# connectors.net
KiCad netlist of a schematic drawn in Altium Designer
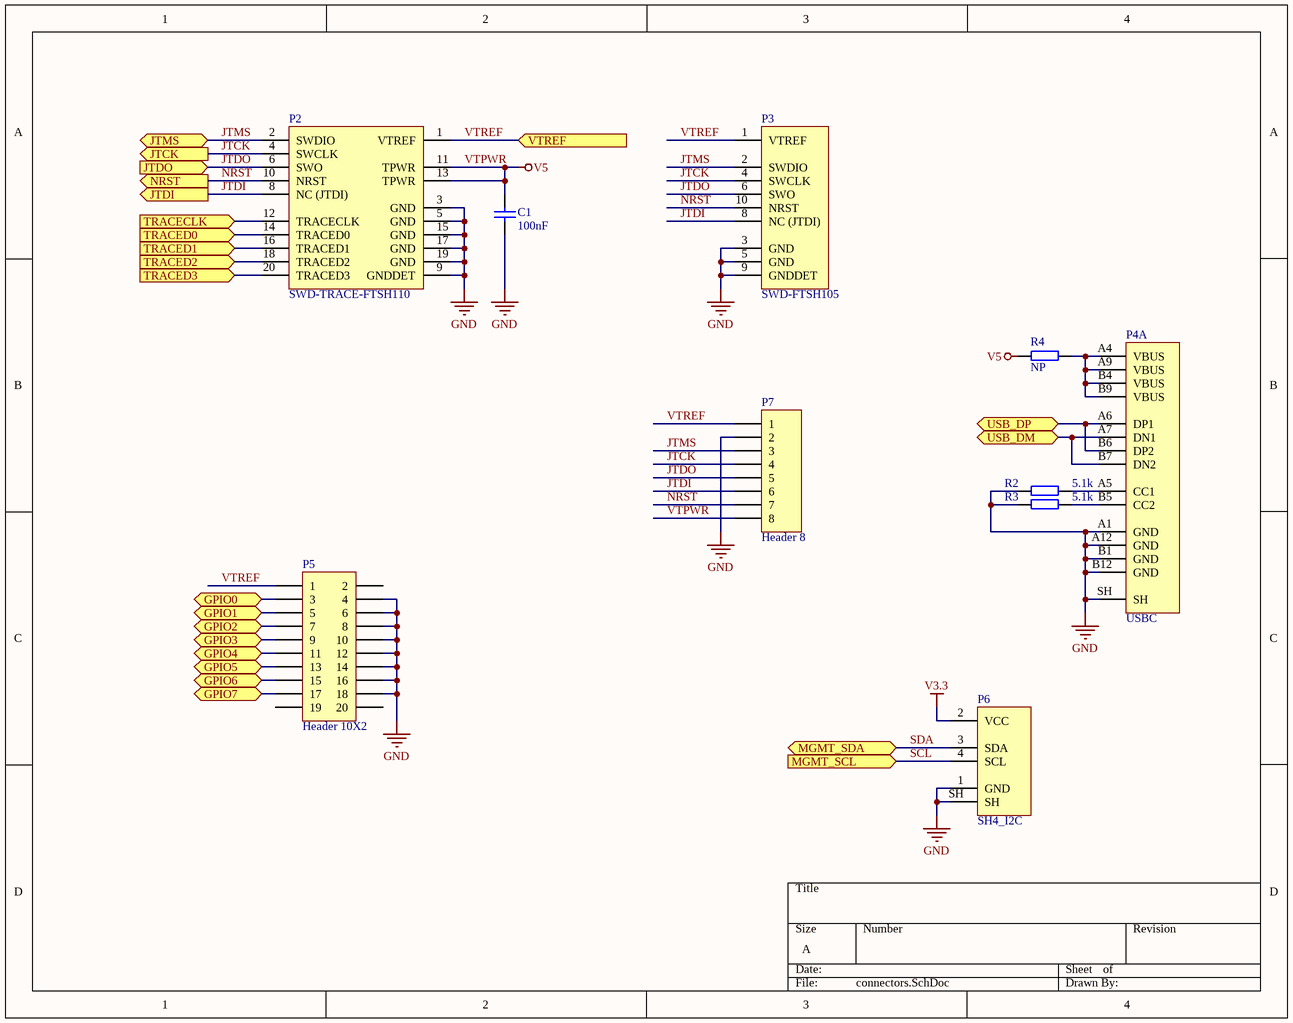
[diagram p0: connectors.SchDoc]

(export (version "E")
  (design (tool "Eeschema 10.0.6"))
  (components
    (comp (ref "C1") (value "100nF") (footprint "0402") (libsource (lib "misc") (part "Capacitor")))
    (comp (ref "P2")
      (value "SWD-TRACE-FTSH110")
      (footprint "FTSH110")
      (libsource (lib "misc") (part "SWD-TRACE-FTSH110"))
    )
    (comp (ref "P3")
      (value "SWD-FTSH105")
      (footprint "FTSH105")
      (libsource (lib "misc") (part "SWD-FTSH105"))
    )
    (comp (ref "P4") (value "USBC") (footprint "U262-161N-4BVC11") (libsource (lib "misc") (part "USBC")))
    (comp (ref "P5")
      (value "Header 10X2")
      (footprint "HDR2X10")
      (description "Header, 10-Pin, Dual row")
      (fields (field (name "PUBLISHER") "Altium Limited"))
      (libsource (lib "Miscellaneous Connectors") (part "Header 10X2"))
    )
    (comp (ref "P6")
      (value "SH4_I2C")
      (footprint "SM04B")
      (description "Qwiic / STEMMA QT Compatible")
      (libsource (lib "misc") (part "SH4_I2C"))
    )
    (comp (ref "P7")
      (value "Header 8")
      (footprint "HDR1X8")
      (description "Header, 8-Pin")
      (fields (field (name "PUBLISHER") "Altium Limited"))
      (libsource (lib "Miscellaneous Connectors") (part "Header 8"))
    )
    (comp (ref "R2") (value "5.1k") (footprint "0402") (libsource (lib "misc") (part "Resistor")))
    (comp (ref "R3") (value "5.1k") (footprint "0402") (libsource (lib "misc") (part "Resistor")))
    (comp (ref "R4") (value "NP") (footprint "0402") (libsource (lib "misc") (part "Resistor")))
  )
  (nets
    (net (code "1") (name "/GPIO0") (class "Default")
      (node (ref "P5") (pin "3") (pinfunction "3_3") (pintype "passive"))
    )
    (net (code "2") (name "/GPIO1") (class "Default")
      (node (ref "P5") (pin "5") (pinfunction "5_5") (pintype "passive"))
    )
    (net (code "3") (name "/GPIO2") (class "Default")
      (node (ref "P5") (pin "7") (pinfunction "7_7") (pintype "passive"))
    )
    (net (code "4") (name "/GPIO3") (class "Default")
      (node (ref "P5") (pin "9") (pinfunction "9_9") (pintype "passive"))
    )
    (net (code "5") (name "/GPIO4") (class "Default")
      (node (ref "P5") (pin "11") (pinfunction "11_11") (pintype "passive"))
    )
    (net (code "6") (name "/GPIO5") (class "Default")
      (node (ref "P5") (pin "13") (pinfunction "13_13") (pintype "passive"))
    )
    (net (code "7") (name "/GPIO6") (class "Default")
      (node (ref "P5") (pin "15") (pinfunction "15_15") (pintype "passive"))
    )
    (net (code "8") (name "/GPIO7") (class "Default")
      (node (ref "P5") (pin "17") (pinfunction "17_17") (pintype "passive"))
    )
    (net (code "9") (name "/JTCK") (class "Default")
      (node (ref "P2") (pin "4") (pinfunction "SWCLK_4") (pintype "passive"))
      (node (ref "P3") (pin "4") (pinfunction "SWCLK_4") (pintype "passive"))
      (node (ref "P7") (pin "4") (pinfunction "4_4") (pintype "passive"))
    )
    (net (code "10") (name "/JTDI") (class "Default")
      (node (ref "P2") (pin "8") (pinfunction "NC_(JTDI)_8") (pintype "passive"))
      (node (ref "P3") (pin "8") (pinfunction "NC_(JTDI)_8") (pintype "passive"))
      (node (ref "P7") (pin "6") (pinfunction "6_6") (pintype "passive"))
    )
    (net (code "11") (name "/JTDO") (class "Default")
      (node (ref "P2") (pin "6") (pinfunction "SWO_6") (pintype "passive"))
      (node (ref "P3") (pin "6") (pinfunction "SWO_6") (pintype "passive"))
      (node (ref "P7") (pin "5") (pinfunction "5_5") (pintype "passive"))
    )
    (net (code "12") (name "/JTMS") (class "Default")
      (node (ref "P2") (pin "2") (pinfunction "SWDIO_2") (pintype "passive"))
      (node (ref "P3") (pin "2") (pinfunction "SWDIO_2") (pintype "passive"))
      (node (ref "P7") (pin "3") (pinfunction "3_3") (pintype "passive"))
    )
    (net (code "13") (name "/NRST") (class "Default")
      (node (ref "P2") (pin "10") (pinfunction "NRST_10") (pintype "passive"))
      (node (ref "P3") (pin "10") (pinfunction "NRST_10") (pintype "passive"))
      (node (ref "P7") (pin "7") (pinfunction "7_7") (pintype "passive"))
    )
    (net (code "14") (name "/SCL") (class "Default")
      (node (ref "P6") (pin "4") (pinfunction "SCL_4") (pintype "passive"))
    )
    (net (code "15") (name "/SDA") (class "Default")
      (node (ref "P6") (pin "3") (pinfunction "SDA_3") (pintype "passive"))
    )
    (net (code "16") (name "/TRACECLK") (class "Default")
      (node (ref "P2") (pin "12") (pinfunction "TRACECLK_12") (pintype "passive"))
    )
    (net (code "17") (name "/TRACED0") (class "Default")
      (node (ref "P2") (pin "14") (pinfunction "TRACED0_14") (pintype "passive"))
    )
    (net (code "18") (name "/TRACED1") (class "Default")
      (node (ref "P2") (pin "16") (pinfunction "TRACED1_16") (pintype "passive"))
    )
    (net (code "19") (name "/TRACED2") (class "Default")
      (node (ref "P2") (pin "18") (pinfunction "TRACED2_18") (pintype "passive"))
    )
    (net (code "20") (name "/TRACED3") (class "Default")
      (node (ref "P2") (pin "20") (pinfunction "TRACED3_20") (pintype "passive"))
    )
    (net (code "21") (name "/USB_DM") (class "Default")
      (node (ref "P4") (pin "A7") (pinfunction "DN1_A7") (pintype "passive"))
      (node (ref "P4") (pin "B7") (pinfunction "DN2_B7") (pintype "passive"))
    )
    (net (code "22") (name "/USB_DP") (class "Default")
      (node (ref "P4") (pin "A6") (pinfunction "DP1_A6") (pintype "passive"))
      (node (ref "P4") (pin "B6") (pinfunction "DP2_B6") (pintype "passive"))
    )
    (net (code "23") (name "/VTREF") (class "Default")
      (node (ref "P2") (pin "1") (pinfunction "VTREF_1") (pintype "passive"))
      (node (ref "P3") (pin "1") (pinfunction "VTREF_1") (pintype "passive"))
      (node (ref "P5") (pin "1") (pinfunction "1_1") (pintype "passive"))
      (node (ref "P7") (pin "1") (pinfunction "1_1") (pintype "passive"))
    )
    (net (code "24") (name "GND") (class "Default")
      (node (ref "C1") (pin "1") (pinfunction "1_1") (pintype "passive"))
      (node (ref "P2") (pin "15") (pinfunction "GND_15") (pintype "passive"))
      (node (ref "P2") (pin "17") (pinfunction "GND_17") (pintype "passive"))
      (node (ref "P2") (pin "19") (pinfunction "GND_19") (pintype "passive"))
      (node (ref "P2") (pin "3") (pinfunction "GND_3") (pintype "passive"))
      (node (ref "P2") (pin "5") (pinfunction "GND_5") (pintype "passive"))
      (node (ref "P2") (pin "9") (pinfunction "GNDDET_9") (pintype "passive"))
      (node (ref "P3") (pin "3") (pinfunction "GND_3") (pintype "passive"))
      (node (ref "P3") (pin "5") (pinfunction "GND_5") (pintype "passive"))
      (node (ref "P3") (pin "9") (pinfunction "GNDDET_9") (pintype "passive"))
      (node (ref "P4") (pin "A1") (pinfunction "GND_A1") (pintype "passive"))
      (node (ref "P4") (pin "A12") (pinfunction "GND_A12") (pintype "passive"))
      (node (ref "P4") (pin "B1") (pinfunction "GND_B1") (pintype "passive"))
      (node (ref "P4") (pin "B12") (pinfunction "GND_B12") (pintype "passive"))
      (node (ref "P4") (pin "SH") (pinfunction "SH_SH") (pintype "passive"))
      (node (ref "P5") (pin "10") (pinfunction "10_10") (pintype "passive"))
      (node (ref "P5") (pin "12") (pinfunction "12_12") (pintype "passive"))
      (node (ref "P5") (pin "14") (pinfunction "14_14") (pintype "passive"))
      (node (ref "P5") (pin "16") (pinfunction "16_16") (pintype "passive"))
      (node (ref "P5") (pin "18") (pinfunction "18_18") (pintype "passive"))
      (node (ref "P5") (pin "4") (pinfunction "4_4") (pintype "passive"))
      (node (ref "P5") (pin "6") (pinfunction "6_6") (pintype "passive"))
      (node (ref "P5") (pin "8") (pinfunction "8_8") (pintype "passive"))
      (node (ref "P6") (pin "1") (pinfunction "GND_1") (pintype "passive"))
      (node (ref "P6") (pin "SH") (pinfunction "SH_SH") (pintype "passive"))
      (node (ref "P7") (pin "2") (pinfunction "2_2") (pintype "passive"))
      (node (ref "R2") (pin "1") (pinfunction "1_1") (pintype "passive"))
      (node (ref "R3") (pin "1") (pinfunction "1_1") (pintype "passive"))
    )
    (net (code "25") (name "Net-(P4A-CC1)") (class "Default")
      (node (ref "P4") (pin "A5") (pinfunction "CC1_A5") (pintype "passive"))
      (node (ref "R2") (pin "2") (pinfunction "2_2") (pintype "passive"))
    )
    (net (code "26") (name "Net-(P4A-CC2)") (class "Default")
      (node (ref "P4") (pin "B5") (pinfunction "CC2_B5") (pintype "passive"))
      (node (ref "R3") (pin "2") (pinfunction "2_2") (pintype "passive"))
    )
    (net (code "27") (name "Net-(P4A-VBUS-PadA4)") (class "Default")
      (node (ref "P4") (pin "A4") (pinfunction "VBUS_A4") (pintype "passive"))
      (node (ref "P4") (pin "A9") (pinfunction "VBUS_A9") (pintype "passive"))
      (node (ref "P4") (pin "B4") (pinfunction "VBUS_B4") (pintype "passive"))
      (node (ref "P4") (pin "B9") (pinfunction "VBUS_B9") (pintype "passive"))
      (node (ref "R4") (pin "2") (pinfunction "2_2") (pintype "passive"))
    )
    (net (code "28") (name "V3.3") (class "Default")
      (node (ref "P6") (pin "2") (pinfunction "VCC_2") (pintype "passive"))
    )
    (net (code "29") (name "V5") (class "Default")
      (node (ref "C1") (pin "2") (pinfunction "2_2") (pintype "passive"))
      (node (ref "P2") (pin "11") (pinfunction "TPWR_11") (pintype "passive"))
      (node (ref "P2") (pin "13") (pinfunction "TPWR_13") (pintype "passive"))
      (node (ref "P7") (pin "8") (pinfunction "8_8") (pintype "passive"))
      (node (ref "R4") (pin "1") (pinfunction "1_1") (pintype "passive"))
    )
    (net (code "30") (name "unconnected-(P5-Pad2)") (class "Default")
      (node (ref "P5") (pin "2") (pinfunction "2_2") (pintype "passive"))
    )
    (net (code "31") (name "unconnected-(P5-Pad19)") (class "Default")
      (node (ref "P5") (pin "19") (pinfunction "19_19") (pintype "passive"))
    )
    (net (code "32") (name "unconnected-(P5-Pad20)") (class "Default")
      (node (ref "P5") (pin "20") (pinfunction "20_20") (pintype "passive"))
    )
  )
)
